# TC_board.net
KiCad netlist of a schematic drawn in EAGLE
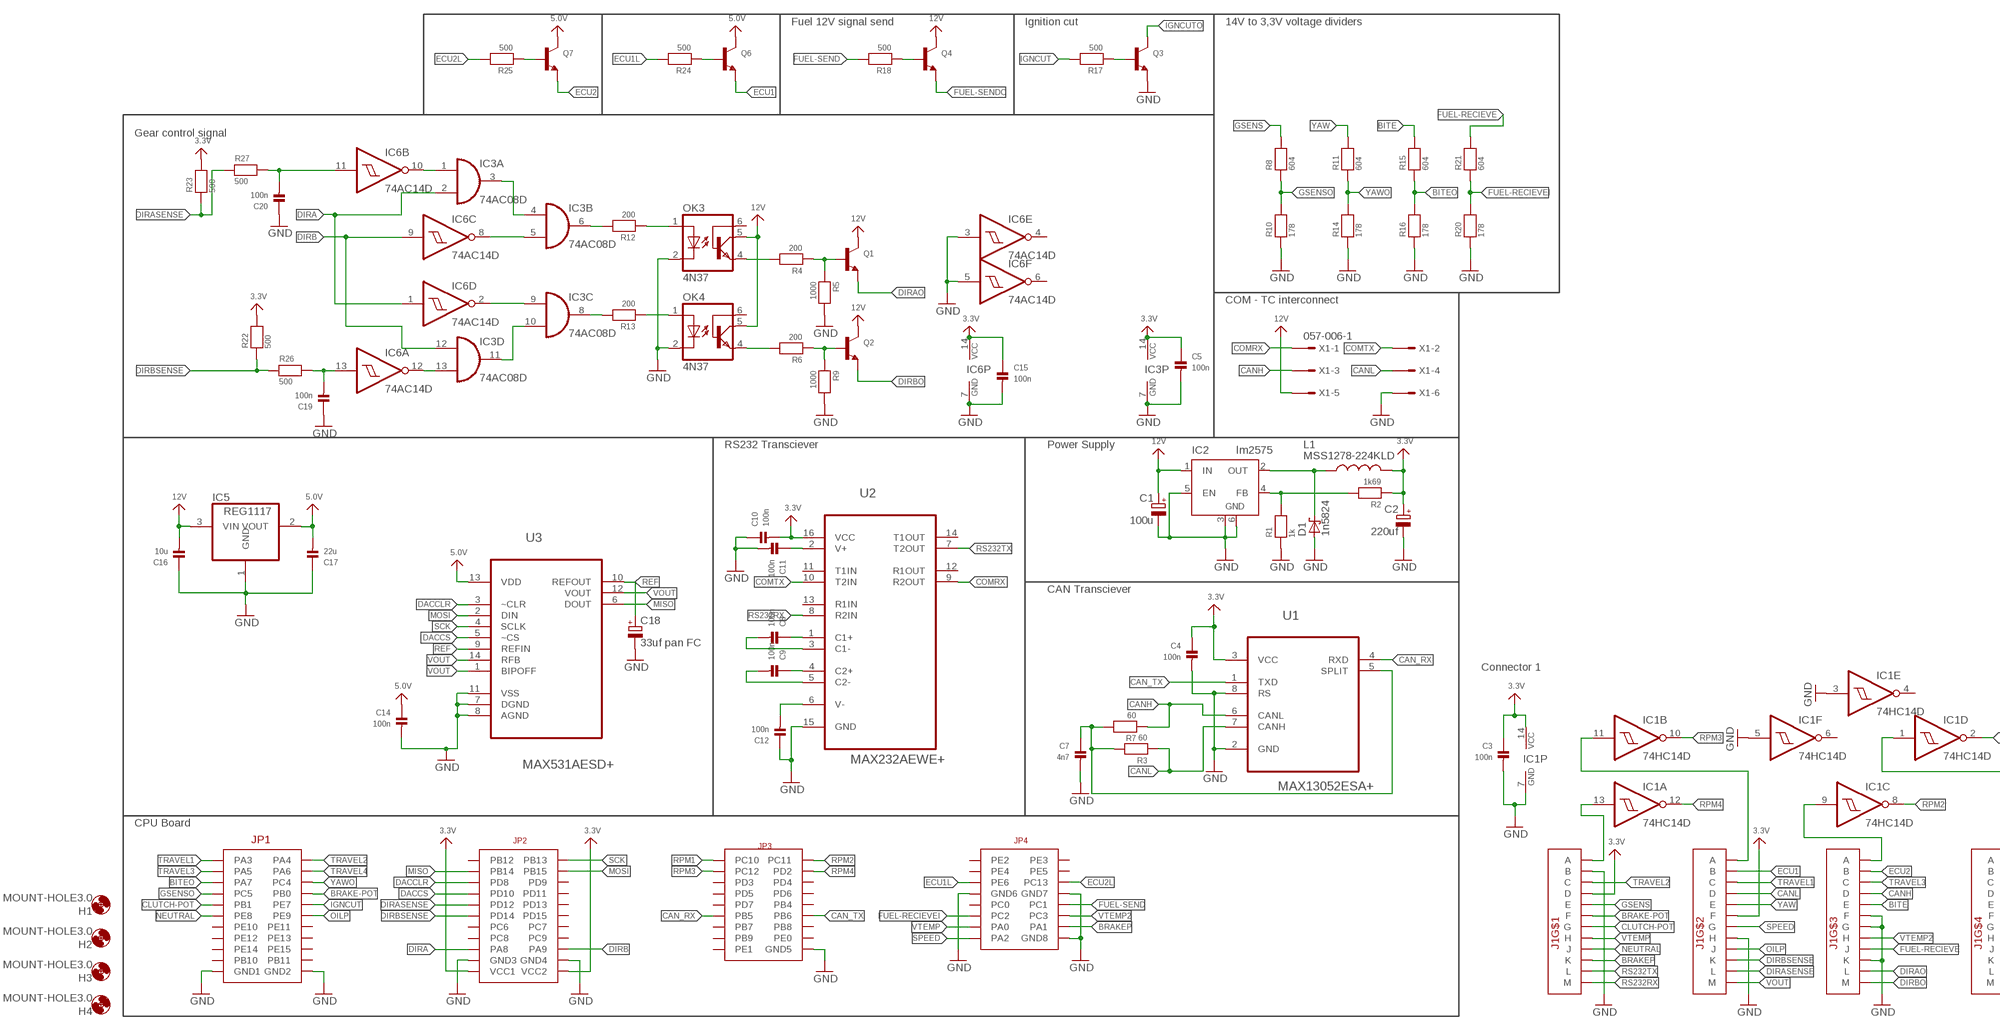
[diagram p0: schematic, sheet 1, part 1 of 2]
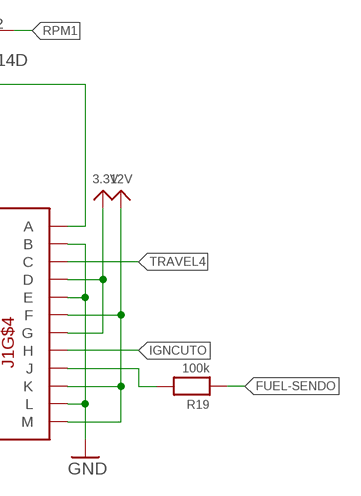
[diagram p1: schematic, sheet 1, part 2 of 2]

(export (version "E")
  (design (tool "Eeschema 10.0.6"))
  (components
    (comp (ref "C1")
      (value "100u")
      (footprint "eagle-import:E2,5-7")
      (libsource (lib "eagle-import") (part "CPOL-EUE2.5-7"))
    )
    (comp (ref "C2")
      (value "220uf")
      (footprint "eagle-import:E3,5-8")
      (libsource (lib "eagle-import") (part "CPOL-EUE3.5-8"))
    )
    (comp (ref "C3")
      (value "100n")
      (footprint "eagle-import:_0603")
      (libsource (lib "eagle-import") (part "CAP_CERAMIC_0603"))
    )
    (comp (ref "C4")
      (value "100n")
      (footprint "eagle-import:_0603")
      (libsource (lib "eagle-import") (part "CAP_CERAMIC_0603"))
    )
    (comp (ref "C5")
      (value "100n")
      (footprint "eagle-import:_0603")
      (libsource (lib "eagle-import") (part "CAP_CERAMIC_0603"))
    )
    (comp (ref "C7")
      (value "4n7")
      (footprint "eagle-import:_0603")
      (libsource (lib "eagle-import") (part "CAP_CERAMIC_0603"))
    )
    (comp (ref "C8")
      (value "100n")
      (footprint "eagle-import:_0603")
      (libsource (lib "eagle-import") (part "CAP_CERAMIC_0603"))
    )
    (comp (ref "C9")
      (value "100n")
      (footprint "eagle-import:_0603")
      (libsource (lib "eagle-import") (part "CAP_CERAMIC_0603"))
    )
    (comp (ref "C10")
      (value "100n")
      (footprint "eagle-import:_0603")
      (libsource (lib "eagle-import") (part "CAP_CERAMIC_0603"))
    )
    (comp (ref "C11")
      (value "100n")
      (footprint "eagle-import:_0603")
      (libsource (lib "eagle-import") (part "CAP_CERAMIC_0603"))
    )
    (comp (ref "C12")
      (value "100n")
      (footprint "eagle-import:_0603")
      (libsource (lib "eagle-import") (part "CAP_CERAMIC_0603"))
    )
    (comp (ref "C14")
      (value "100n")
      (footprint "eagle-import:_0603")
      (libsource (lib "eagle-import") (part "CAP_CERAMIC_0603"))
    )
    (comp (ref "C15")
      (value "100n")
      (footprint "eagle-import:_0603")
      (libsource (lib "eagle-import") (part "CAP_CERAMIC_0603"))
    )
    (comp (ref "C16")
      (value "10u")
      (footprint "eagle-import:_0805")
      (libsource (lib "eagle-import") (part "CAP_CERAMIC_0805"))
    )
    (comp (ref "C17")
      (value "22u")
      (footprint "eagle-import:_0805")
      (libsource (lib "eagle-import") (part "CAP_CERAMIC_0805"))
    )
    (comp (ref "C18")
      (value "33uf pan FC")
      (footprint "eagle-import:UD-5X5,8_NICHICON")
      (libsource (lib "eagle-import") (part "CPOL-EUUD-5X5,8"))
    )
    (comp (ref "C19")
      (value "100n")
      (footprint "eagle-import:_0805")
      (libsource (lib "eagle-import") (part "CAP_CERAMIC_0805"))
    )
    (comp (ref "C20")
      (value "100n")
      (footprint "eagle-import:_0805")
      (libsource (lib "eagle-import") (part "CAP_CERAMIC_0805"))
    )
    (comp (ref "D1")
      (value "1n5824")
      (footprint "eagle-import:F126Z12")
      (libsource (lib "eagle-import") (part "SCHOTTKY-DIODEF126Z12"))
    )
    (comp (ref "H1")
      (value "MOUNT-HOLE3.0")
      (footprint "eagle-import:3,0")
      (libsource (lib "eagle-import") (part "MOUNT-HOLE3.0"))
    )
    (comp (ref "H2")
      (value "MOUNT-HOLE3.0")
      (footprint "eagle-import:3,0")
      (libsource (lib "eagle-import") (part "MOUNT-HOLE3.0"))
    )
    (comp (ref "H3")
      (value "MOUNT-HOLE3.0")
      (footprint "eagle-import:3,0")
      (libsource (lib "eagle-import") (part "MOUNT-HOLE3.0"))
    )
    (comp (ref "H4")
      (value "MOUNT-HOLE3.0")
      (footprint "eagle-import:3,0")
      (libsource (lib "eagle-import") (part "MOUNT-HOLE3.0"))
    )
    (comp (ref "IC1")
      (value "74HC14D")
      (footprint "eagle-import:SO14")
      (libsource (lib "eagle-import") (part "7414DHC"))
    )
    (comp (ref "IC2")
      (value "lm2575")
      (footprint "eagle-import:TO263-5")
      (libsource (lib "eagle-import") (part "LM2596S"))
    )
    (comp (ref "IC3")
      (value "74AC08D")
      (footprint "eagle-import:SO14")
      (libsource (lib "eagle-import") (part "7408DAC"))
    )
    (comp (ref "IC5")
      (value "REG1117")
      (footprint "eagle-import:SOT223")
      (libsource (lib "eagle-import") (part "REG1117"))
    )
    (comp (ref "IC6")
      (value "74AC14D")
      (footprint "eagle-import:SO14")
      (libsource (lib "eagle-import") (part "7414DAC"))
    )
    (comp (ref "J1")
      (value "CON1")
      (footprint "eagle-import:AUTOCONNECTOR")
      (libsource (lib "eagle-import") (part "AUTOCONNECTOR"))
    )
    (comp (ref "L1")
      (value "MSS1278-224KLD")
      (footprint "eagle-import:CDRH125")
      (libsource (lib "eagle-import") (part "INDUCTORPWR"))
    )
    (comp (ref "OK3")
      (value "4N37")
      (footprint "eagle-import:DIL06")
      (fields (field (name "MF") "FAIRCHILD SEMICONDUCTOR"))
      (libsource (lib "eagle-import") (part "4N37"))
    )
    (comp (ref "OK4")
      (value "4N37")
      (footprint "eagle-import:DIL06")
      (fields (field (name "MF") "FAIRCHILD SEMICONDUCTOR"))
      (libsource (lib "eagle-import") (part "4N37"))
    )
    (comp (ref "Q1")
      (value "TRANSISTOR_NPNWIDE")
      (footprint "eagle-import:SOT23-WIDE")
      (libsource (lib "eagle-import") (part "TRANSISTOR_NPNWIDE"))
    )
    (comp (ref "Q2")
      (value "TRANSISTOR_NPNWIDE")
      (footprint "eagle-import:SOT23-WIDE")
      (libsource (lib "eagle-import") (part "TRANSISTOR_NPNWIDE"))
    )
    (comp (ref "Q3")
      (value "TRANSISTOR_NPNWIDE")
      (footprint "eagle-import:SOT23-WIDE")
      (libsource (lib "eagle-import") (part "TRANSISTOR_NPNWIDE"))
    )
    (comp (ref "Q4")
      (value "TRANSISTOR_NPNWIDE")
      (footprint "eagle-import:SOT23-WIDE")
      (libsource (lib "eagle-import") (part "TRANSISTOR_NPNWIDE"))
    )
    (comp (ref "Q6")
      (value "TRANSISTOR_NPNWIDE")
      (footprint "eagle-import:SOT23-WIDE")
      (libsource (lib "eagle-import") (part "TRANSISTOR_NPNWIDE"))
    )
    (comp (ref "Q7")
      (value "TRANSISTOR_NPNWIDE")
      (footprint "eagle-import:SOT23-WIDE")
      (libsource (lib "eagle-import") (part "TRANSISTOR_NPNWIDE"))
    )
    (comp (ref "R1")
      (value "1k")
      (footprint "eagle-import:_0603")
      (libsource (lib "eagle-import") (part "RESISTOR_0603"))
    )
    (comp (ref "R2")
      (value "1k69")
      (footprint "eagle-import:_0603")
      (libsource (lib "eagle-import") (part "RESISTOR_0603"))
    )
    (comp (ref "R3")
      (value "60")
      (footprint "eagle-import:_0603")
      (libsource (lib "eagle-import") (part "RESISTOR_0603"))
    )
    (comp (ref "R4")
      (value "200")
      (footprint "eagle-import:_0603")
      (libsource (lib "eagle-import") (part "RESISTOR_0603"))
    )
    (comp (ref "R5")
      (value "1000")
      (footprint "eagle-import:_0603")
      (libsource (lib "eagle-import") (part "RESISTOR_0603"))
    )
    (comp (ref "R6")
      (value "200")
      (footprint "eagle-import:_0603")
      (libsource (lib "eagle-import") (part "RESISTOR_0603"))
    )
    (comp (ref "R7")
      (value "60")
      (footprint "eagle-import:_0603")
      (libsource (lib "eagle-import") (part "RESISTOR_0603"))
    )
    (comp (ref "R8")
      (value "604")
      (footprint "eagle-import:_0603")
      (libsource (lib "eagle-import") (part "RESISTOR_0603"))
    )
    (comp (ref "R9")
      (value "1000")
      (footprint "eagle-import:_0603")
      (libsource (lib "eagle-import") (part "RESISTOR_0603"))
    )
    (comp (ref "R10")
      (value "178")
      (footprint "eagle-import:_0603")
      (libsource (lib "eagle-import") (part "RESISTOR_0603"))
    )
    (comp (ref "R11")
      (value "604")
      (footprint "eagle-import:_0603")
      (libsource (lib "eagle-import") (part "RESISTOR_0603"))
    )
    (comp (ref "R12")
      (value "200")
      (footprint "eagle-import:_0603")
      (libsource (lib "eagle-import") (part "RESISTOR_0603"))
    )
    (comp (ref "R13")
      (value "200")
      (footprint "eagle-import:_0603")
      (libsource (lib "eagle-import") (part "RESISTOR_0603"))
    )
    (comp (ref "R14")
      (value "178")
      (footprint "eagle-import:_0603")
      (libsource (lib "eagle-import") (part "RESISTOR_0603"))
    )
    (comp (ref "R15")
      (value "604")
      (footprint "eagle-import:_0603")
      (libsource (lib "eagle-import") (part "RESISTOR_0603"))
    )
    (comp (ref "R16")
      (value "178")
      (footprint "eagle-import:_0603")
      (libsource (lib "eagle-import") (part "RESISTOR_0603"))
    )
    (comp (ref "R17")
      (value "500")
      (footprint "eagle-import:_0603")
      (libsource (lib "eagle-import") (part "RESISTOR_0603"))
    )
    (comp (ref "R18")
      (value "500")
      (footprint "eagle-import:_0603")
      (libsource (lib "eagle-import") (part "RESISTOR_0603"))
    )
    (comp (ref "R19")
      (value "100k")
      (footprint "eagle-import:_0603")
      (libsource (lib "eagle-import") (part "RESISTOR_0603"))
    )
    (comp (ref "R20")
      (value "178")
      (footprint "eagle-import:_0603")
      (libsource (lib "eagle-import") (part "RESISTOR_0603"))
    )
    (comp (ref "R21")
      (value "604")
      (footprint "eagle-import:_0603")
      (libsource (lib "eagle-import") (part "RESISTOR_0603"))
    )
    (comp (ref "R22")
      (value "500")
      (footprint "eagle-import:_0603")
      (libsource (lib "eagle-import") (part "RESISTOR_0603"))
    )
    (comp (ref "R23")
      (value "500")
      (footprint "eagle-import:_0603")
      (libsource (lib "eagle-import") (part "RESISTOR_0603"))
    )
    (comp (ref "R24")
      (value "500")
      (footprint "eagle-import:_0603")
      (libsource (lib "eagle-import") (part "RESISTOR_0603"))
    )
    (comp (ref "R25")
      (value "500")
      (footprint "eagle-import:_0603")
      (libsource (lib "eagle-import") (part "RESISTOR_0603"))
    )
    (comp (ref "R26")
      (value "500")
      (footprint "eagle-import:_0603")
      (libsource (lib "eagle-import") (part "RESISTOR_0603"))
    )
    (comp (ref "R27")
      (value "500")
      (footprint "eagle-import:_0603")
      (libsource (lib "eagle-import") (part "RESISTOR_0603"))
    )
    (comp (ref "U$1")
      (value "CPU-BOARD")
      (footprint "eagle-import:CPU-BOARD-JP1")
      (libsource (lib "eagle-import") (part "CPU-BOARD"))
    )
    (comp (ref "U1")
      (value "MAX13052ESA+")
      (footprint "eagle-import:SOIC127P600X175-8N")
      (libsource (lib "eagle-import") (part "MAX13052ESA+"))
    )
    (comp (ref "U2")
      (value "MAX232AEWE+")
      (footprint "eagle-import:SOIC127P1032X265-16N")
      (libsource (lib "eagle-import") (part "MAX232AEWE+"))
    )
    (comp (ref "U3")
      (value "MAX531AESD+")
      (footprint "eagle-import:SOIC127P600X175-14N")
      (libsource (lib "eagle-import") (part "MAX531AESD+"))
    )
    (comp (ref "X1")
      (value "057-006-1")
      (footprint "eagle-import:057-006-1")
      (libsource (lib "eagle-import") (part "057-006-1"))
    )
  )
  (nets
    (net (code "1") (name "3.3V") (class "Default")
      (node (ref "C10") (pin "2") (pinfunction "P$2_2") (pintype "passive"))
      (node (ref "C15") (pin "1") (pinfunction "P$1_1") (pintype "passive"))
      (node (ref "C2") (pin "+") (pinfunction "+_+") (pintype "passive"))
      (node (ref "C3") (pin "1") (pinfunction "P$1_1") (pintype "passive"))
      (node (ref "C4") (pin "1") (pinfunction "P$1_1") (pintype "passive"))
      (node (ref "C5") (pin "1") (pinfunction "P$1_1") (pintype "passive"))
      (node (ref "IC1") (pin "14") (pinfunction "VCC_14") (pintype "power_in"))
      (node (ref "IC3") (pin "14") (pinfunction "VCC_14") (pintype "power_in"))
      (node (ref "IC6") (pin "14") (pinfunction "VCC_14") (pintype "power_in"))
      (node (ref "J1") (pin "D1") (pinfunction "D_D1") (pintype "bidirectional"))
      (node (ref "J1") (pin "D4") (pinfunction "D_D4") (pintype "bidirectional"))
      (node (ref "J1") (pin "F2") (pinfunction "F_F2") (pintype "bidirectional"))
      (node (ref "J1") (pin "G4") (pinfunction "G_G4") (pintype "bidirectional"))
      (node (ref "L1") (pin "2") (pinfunction "2_2") (pintype "passive"))
      (node (ref "R2") (pin "1") (pinfunction "1_1") (pintype "passive"))
      (node (ref "R22") (pin "2") (pinfunction "2_2") (pintype "passive"))
      (node (ref "R23") (pin "2") (pinfunction "2_2") (pintype "passive"))
      (node (ref "U$1") (pin "P$43") (pinfunction "VCC1_P$43") (pintype "bidirectional"))
      (node (ref "U$1") (pin "P$44") (pinfunction "VCC2_P$44") (pintype "bidirectional"))
      (node (ref "U1") (pin "3") (pinfunction "VCC_3") (pintype "power_in"))
      (node (ref "U2") (pin "16") (pinfunction "VCC_16") (pintype "power_in"))
    )
    (net (code "2") (name "5.0V") (class "Default")
      (node (ref "C14") (pin "1") (pinfunction "P$1_1") (pintype "passive"))
      (node (ref "C17") (pin "2") (pinfunction "P$2_2") (pintype "passive"))
      (node (ref "IC5") (pin "2") (pinfunction "VOUT_2") (pintype "output"))
      (node (ref "Q6") (pin "3") (pinfunction "C_3") (pintype "passive"))
      (node (ref "Q7") (pin "3") (pinfunction "C_3") (pintype "passive"))
      (node (ref "U3") (pin "13") (pinfunction "VDD_13") (pintype "power_in"))
    )
    (net (code "3") (name "12V") (class "Default")
      (node (ref "C1") (pin "+") (pinfunction "+_+") (pintype "passive"))
      (node (ref "C16") (pin "2") (pinfunction "P$2_2") (pintype "passive"))
      (node (ref "IC2") (pin "1") (pinfunction "IN_1") (pintype "input"))
      (node (ref "IC5") (pin "3") (pinfunction "VIN_3") (pintype "input"))
      (node (ref "J1") (pin "F4") (pinfunction "F_F4") (pintype "bidirectional"))
      (node (ref "J1") (pin "K4") (pinfunction "K_K4") (pintype "bidirectional"))
      (node (ref "J1") (pin "M4") (pinfunction "M_M4") (pintype "bidirectional"))
      (node (ref "OK3") (pin "5") (pinfunction "COL_5") (pintype "passive"))
      (node (ref "OK4") (pin "5") (pinfunction "COL_5") (pintype "passive"))
      (node (ref "Q1") (pin "3") (pinfunction "C_3") (pintype "passive"))
      (node (ref "Q2") (pin "3") (pinfunction "C_3") (pintype "passive"))
      (node (ref "Q4") (pin "3") (pinfunction "C_3") (pintype "passive"))
      (node (ref "X1") (pin "5") (pinfunction "S_5") (pintype "passive"))
    )
    (net (code "4") (name "BITE") (class "Default")
      (node (ref "J1") (pin "E3") (pinfunction "E_E3") (pintype "bidirectional"))
      (node (ref "R15") (pin "2") (pinfunction "2_2") (pintype "passive"))
    )
    (net (code "5") (name "BITEO") (class "Default")
      (node (ref "R15") (pin "1") (pinfunction "1_1") (pintype "passive"))
      (node (ref "R16") (pin "2") (pinfunction "2_2") (pintype "passive"))
      (node (ref "U$1") (pin "P$5") (pinfunction "PA7_P$5") (pintype "bidirectional"))
    )
    (net (code "6") (name "BRAKE-POT") (class "Default")
      (node (ref "J1") (pin "F1") (pinfunction "F_F1") (pintype "bidirectional"))
      (node (ref "U$1") (pin "P$8") (pinfunction "PB0_P$8") (pintype "bidirectional"))
    )
    (net (code "7") (name "BRAKEP") (class "Default")
      (node (ref "J1") (pin "K1") (pinfunction "K_K1") (pintype "bidirectional"))
      (node (ref "U$1") (pin "P$76") (pinfunction "PA1_P$76") (pintype "bidirectional"))
    )
    (net (code "8") (name "CANH") (class "Default")
      (node (ref "J1") (pin "D3") (pinfunction "D_D3") (pintype "bidirectional"))
      (node (ref "R7") (pin "1") (pinfunction "1_1") (pintype "passive"))
      (node (ref "U1") (pin "6") (pinfunction "CANL_6") (pintype "input"))
      (node (ref "X1") (pin "3") (pinfunction "S_3") (pintype "passive"))
    )
    (net (code "9") (name "CANL") (class "Default")
      (node (ref "J1") (pin "D2") (pinfunction "D_D2") (pintype "bidirectional"))
      (node (ref "R3") (pin "1") (pinfunction "1_1") (pintype "passive"))
      (node (ref "U1") (pin "7") (pinfunction "CANH_7") (pintype "input"))
      (node (ref "X1") (pin "4") (pinfunction "S_4") (pintype "passive"))
    )
    (net (code "10") (name "CAN_RX") (class "Default")
      (node (ref "U$1") (pin "P$55") (pinfunction "PB5_P$55") (pintype "bidirectional"))
      (node (ref "U1") (pin "4") (pinfunction "RXD_4") (pintype "output"))
    )
    (net (code "11") (name "CAN_TX") (class "Default")
      (node (ref "U$1") (pin "P$56") (pinfunction "PB6_P$56") (pintype "bidirectional"))
      (node (ref "U1") (pin "1") (pinfunction "TXD_1") (pintype "input"))
    )
    (net (code "12") (name "CLUTCH-POT") (class "Default")
      (node (ref "J1") (pin "G1") (pinfunction "G_G1") (pintype "bidirectional"))
      (node (ref "U$1") (pin "P$9") (pinfunction "PB1_P$9") (pintype "bidirectional"))
    )
    (net (code "13") (name "COMRX") (class "Default")
      (node (ref "U2") (pin "9") (pinfunction "R2OUT_9") (pintype "output"))
      (node (ref "X1") (pin "1") (pinfunction "S_1") (pintype "passive"))
    )
    (net (code "14") (name "COMTX") (class "Default")
      (node (ref "U2") (pin "10") (pinfunction "T2IN_10") (pintype "input"))
      (node (ref "X1") (pin "2") (pinfunction "S_2") (pintype "passive"))
    )
    (net (code "15") (name "DACCLR") (class "Default")
      (node (ref "U$1") (pin "P$27") (pinfunction "PD8_P$27") (pintype "bidirectional"))
      (node (ref "U3") (pin "3") (pinfunction "~{CLR}_3") (pintype "input"))
    )
    (net (code "16") (name "DACCS") (class "Default")
      (node (ref "U$1") (pin "P$29") (pinfunction "PD10_P$29") (pintype "bidirectional"))
      (node (ref "U3") (pin "5") (pinfunction "~{CS}_5") (pintype "input"))
    )
    (net (code "17") (name "DIRA") (class "Default")
      (node (ref "IC3") (pin "2") (pinfunction "I1_2") (pintype "input"))
      (node (ref "IC6") (pin "1") (pinfunction "I_1") (pintype "input"))
      (node (ref "U$1") (pin "P$39") (pinfunction "PA8_P$39") (pintype "bidirectional"))
    )
    (net (code "18") (name "DIRAO") (class "Default")
      (node (ref "J1") (pin "L3") (pinfunction "L_L3") (pintype "bidirectional"))
      (node (ref "Q1") (pin "2") (pinfunction "E_2") (pintype "passive"))
    )
    (net (code "19") (name "DIRASENSE") (class "Default")
      (node (ref "J1") (pin "L2") (pinfunction "L_L2") (pintype "bidirectional"))
      (node (ref "R23") (pin "1") (pinfunction "1_1") (pintype "passive"))
      (node (ref "R27") (pin "1") (pinfunction "1_1") (pintype "passive"))
      (node (ref "U$1") (pin "P$31") (pinfunction "PD12_P$31") (pintype "bidirectional"))
    )
    (net (code "20") (name "DIRB") (class "Default")
      (node (ref "IC3") (pin "12") (pinfunction "I0_12") (pintype "input"))
      (node (ref "IC6") (pin "9") (pinfunction "I_9") (pintype "input"))
      (node (ref "U$1") (pin "P$40") (pinfunction "PA9_P$40") (pintype "bidirectional"))
    )
    (net (code "21") (name "DIRBO") (class "Default")
      (node (ref "J1") (pin "M3") (pinfunction "M_M3") (pintype "bidirectional"))
      (node (ref "Q2") (pin "2") (pinfunction "E_2") (pintype "passive"))
    )
    (net (code "22") (name "DIRBSENSE") (class "Default")
      (node (ref "J1") (pin "K2") (pinfunction "K_K2") (pintype "bidirectional"))
      (node (ref "R22") (pin "1") (pinfunction "1_1") (pintype "passive"))
      (node (ref "R26") (pin "1") (pinfunction "1_1") (pintype "passive"))
      (node (ref "U$1") (pin "P$33") (pinfunction "PD14_P$33") (pintype "bidirectional"))
    )
    (net (code "23") (name "ECU1") (class "Default")
      (node (ref "J1") (pin "B2") (pinfunction "B_B2") (pintype "bidirectional"))
      (node (ref "Q6") (pin "2") (pinfunction "E_2") (pintype "passive"))
    )
    (net (code "24") (name "ECU1L") (class "Default")
      (node (ref "R24") (pin "2") (pinfunction "2_2") (pintype "passive"))
      (node (ref "U$1") (pin "P$67") (pinfunction "PE6_P$67") (pintype "bidirectional"))
    )
    (net (code "25") (name "ECU2") (class "Default")
      (node (ref "J1") (pin "B3") (pinfunction "B_B3") (pintype "bidirectional"))
      (node (ref "Q7") (pin "2") (pinfunction "E_2") (pintype "passive"))
    )
    (net (code "26") (name "ECU2L") (class "Default")
      (node (ref "R25") (pin "2") (pinfunction "2_2") (pintype "passive"))
      (node (ref "U$1") (pin "P$68") (pinfunction "PC13_P$68") (pintype "bidirectional"))
    )
    (net (code "27") (name "FUEL-RECIEVE") (class "Default")
      (node (ref "J1") (pin "J3") (pinfunction "J_J3") (pintype "bidirectional"))
      (node (ref "R21") (pin "2") (pinfunction "2_2") (pintype "passive"))
    )
    (net (code "28") (name "FUEL-RECIEVEI") (class "Default")
      (node (ref "R20") (pin "2") (pinfunction "2_2") (pintype "passive"))
      (node (ref "R21") (pin "1") (pinfunction "1_1") (pintype "passive"))
      (node (ref "U$1") (pin "P$73") (pinfunction "PC2_P$73") (pintype "bidirectional"))
    )
    (net (code "29") (name "FUEL-SEND") (class "Default")
      (node (ref "R18") (pin "2") (pinfunction "2_2") (pintype "passive"))
      (node (ref "U$1") (pin "P$72") (pinfunction "PC1_P$72") (pintype "bidirectional"))
    )
    (net (code "30") (name "FUEL-SENDO") (class "Default")
      (node (ref "Q4") (pin "2") (pinfunction "E_2") (pintype "passive"))
      (node (ref "R19") (pin "1") (pinfunction "1_1") (pintype "passive"))
    )
    (net (code "31") (name "GND") (class "Default")
      (node (ref "C1") (pin "-") (pinfunction "-_-") (pintype "passive"))
      (node (ref "C10") (pin "1") (pinfunction "P$1_1") (pintype "passive"))
      (node (ref "C11") (pin "2") (pinfunction "P$2_2") (pintype "passive"))
      (node (ref "C12") (pin "1") (pinfunction "P$1_1") (pintype "passive"))
      (node (ref "C14") (pin "2") (pinfunction "P$2_2") (pintype "passive"))
      (node (ref "C15") (pin "2") (pinfunction "P$2_2") (pintype "passive"))
      (node (ref "C16") (pin "1") (pinfunction "P$1_1") (pintype "passive"))
      (node (ref "C17") (pin "1") (pinfunction "P$1_1") (pintype "passive"))
      (node (ref "C18") (pin "-") (pinfunction "-_-") (pintype "passive"))
      (node (ref "C19") (pin "1") (pinfunction "P$1_1") (pintype "passive"))
      (node (ref "C2") (pin "-") (pinfunction "-_-") (pintype "passive"))
      (node (ref "C20") (pin "1") (pinfunction "P$1_1") (pintype "passive"))
      (node (ref "C3") (pin "2") (pinfunction "P$2_2") (pintype "passive"))
      (node (ref "C4") (pin "2") (pinfunction "P$2_2") (pintype "passive"))
      (node (ref "C5") (pin "2") (pinfunction "P$2_2") (pintype "passive"))
      (node (ref "C7") (pin "2") (pinfunction "P$2_2") (pintype "passive"))
      (node (ref "D1") (pin "A") (pinfunction "A_A") (pintype "passive"))
      (node (ref "IC1") (pin "3") (pinfunction "I_3") (pintype "input"))
      (node (ref "IC1") (pin "5") (pinfunction "I_5") (pintype "input"))
      (node (ref "IC1") (pin "7") (pinfunction "GND_7") (pintype "power_in"))
      (node (ref "IC2") (pin "3") (pinfunction "GND_3") (pintype "power_in"))
      (node (ref "IC2") (pin "5") (pinfunction "EN_5") (pintype "input"))
      (node (ref "IC2") (pin "6") (pinfunction "GND_6") (pintype "power_in"))
      (node (ref "IC3") (pin "7") (pinfunction "GND_7") (pintype "power_in"))
      (node (ref "IC5") (pin "1") (pinfunction "GND_1") (pintype "power_in"))
      (node (ref "IC6") (pin "3") (pinfunction "I_3") (pintype "input"))
      (node (ref "IC6") (pin "5") (pinfunction "I_5") (pintype "input"))
      (node (ref "IC6") (pin "7") (pinfunction "GND_7") (pintype "power_in"))
      (node (ref "J1") (pin "B1") (pinfunction "B_B1") (pintype "bidirectional"))
      (node (ref "J1") (pin "B4") (pinfunction "B_B4") (pintype "bidirectional"))
      (node (ref "J1") (pin "E4") (pinfunction "E_E4") (pintype "bidirectional"))
      (node (ref "J1") (pin "F3") (pinfunction "F_F3") (pintype "bidirectional"))
      (node (ref "J1") (pin "G3") (pinfunction "G_G3") (pintype "bidirectional"))
      (node (ref "J1") (pin "H2") (pinfunction "H_H2") (pintype "bidirectional"))
      (node (ref "J1") (pin "K3") (pinfunction "K_K3") (pintype "bidirectional"))
      (node (ref "J1") (pin "L4") (pinfunction "L_L4") (pintype "bidirectional"))
      (node (ref "OK3") (pin "2") (pinfunction "C_2") (pintype "passive"))
      (node (ref "OK4") (pin "2") (pinfunction "C_2") (pintype "passive"))
      (node (ref "Q3") (pin "2") (pinfunction "E_2") (pintype "passive"))
      (node (ref "R1") (pin "1") (pinfunction "1_1") (pintype "passive"))
      (node (ref "R10") (pin "1") (pinfunction "1_1") (pintype "passive"))
      (node (ref "R14") (pin "1") (pinfunction "1_1") (pintype "passive"))
      (node (ref "R16") (pin "1") (pinfunction "1_1") (pintype "passive"))
      (node (ref "R20") (pin "1") (pinfunction "1_1") (pintype "passive"))
      (node (ref "R5") (pin "2") (pinfunction "2_2") (pintype "passive"))
      (node (ref "R9") (pin "2") (pinfunction "2_2") (pintype "passive"))
      (node (ref "U$1") (pin "P$19") (pinfunction "GND1_P$19") (pintype "bidirectional"))
      (node (ref "U$1") (pin "P$20") (pinfunction "GND2_P$20") (pintype "bidirectional"))
      (node (ref "U$1") (pin "P$41") (pinfunction "GND3_P$41") (pintype "bidirectional"))
      (node (ref "U$1") (pin "P$42") (pinfunction "GND4_P$42") (pintype "bidirectional"))
      (node (ref "U$1") (pin "P$62") (pinfunction "GND5_P$62") (pintype "bidirectional"))
      (node (ref "U$1") (pin "P$69") (pinfunction "GND6_P$69") (pintype "bidirectional"))
      (node (ref "U$1") (pin "P$70") (pinfunction "GND7_P$70") (pintype "bidirectional"))
      (node (ref "U$1") (pin "P$78") (pinfunction "GND8_P$78") (pintype "bidirectional"))
      (node (ref "U1") (pin "2") (pinfunction "GND_2") (pintype "passive"))
      (node (ref "U1") (pin "8") (pinfunction "RS_8") (pintype "input"))
      (node (ref "U2") (pin "15") (pinfunction "GND_15") (pintype "passive"))
      (node (ref "U3") (pin "11") (pinfunction "VSS_11") (pintype "power_in"))
      (node (ref "U3") (pin "7") (pinfunction "DGND_7") (pintype "passive"))
      (node (ref "U3") (pin "8") (pinfunction "AGND_8") (pintype "passive"))
      (node (ref "X1") (pin "6") (pinfunction "S_6") (pintype "passive"))
    )
    (net (code "32") (name "GSENS") (class "Default")
      (node (ref "J1") (pin "E1") (pinfunction "E_E1") (pintype "bidirectional"))
      (node (ref "R8") (pin "2") (pinfunction "2_2") (pintype "passive"))
    )
    (net (code "33") (name "GSENSO") (class "Default")
      (node (ref "R10") (pin "2") (pinfunction "2_2") (pintype "passive"))
      (node (ref "R8") (pin "1") (pinfunction "1_1") (pintype "passive"))
      (node (ref "U$1") (pin "P$7") (pinfunction "PC5_P$7") (pintype "bidirectional"))
    )
    (net (code "34") (name "IGNCUT") (class "Default")
      (node (ref "R17") (pin "2") (pinfunction "2_2") (pintype "passive"))
      (node (ref "U$1") (pin "P$10") (pinfunction "PE7_P$10") (pintype "bidirectional"))
    )
    (net (code "35") (name "IGNCUTO") (class "Default")
      (node (ref "J1") (pin "H4") (pinfunction "H_H4") (pintype "bidirectional"))
      (node (ref "Q3") (pin "3") (pinfunction "C_3") (pintype "passive"))
    )
    (net (code "36") (name "MISO") (class "Default")
      (node (ref "U$1") (pin "P$25") (pinfunction "PB14_P$25") (pintype "bidirectional"))
      (node (ref "U3") (pin "6") (pinfunction "DOUT_6") (pintype "output"))
    )
    (net (code "37") (name "MOSI") (class "Default")
      (node (ref "U$1") (pin "P$26") (pinfunction "PB15_P$26") (pintype "bidirectional"))
      (node (ref "U3") (pin "2") (pinfunction "DIN_2") (pintype "input"))
    )
    (net (code "38") (name "NEUTRAL") (class "Default")
      (node (ref "J1") (pin "J1") (pinfunction "J_J1") (pintype "bidirectional"))
      (node (ref "U$1") (pin "P$11") (pinfunction "PE8_P$11") (pintype "bidirectional"))
    )
    (net (code "39") (name "Net-(C7-P$1)") (class "Default")
      (node (ref "C7") (pin "1") (pinfunction "P$1_1") (pintype "passive"))
      (node (ref "R3") (pin "2") (pinfunction "2_2") (pintype "passive"))
      (node (ref "R7") (pin "2") (pinfunction "2_2") (pintype "passive"))
      (node (ref "U1") (pin "5") (pinfunction "SPLIT_5") (pintype "output"))
    )
    (net (code "40") (name "Net-(C8-P$1)") (class "Default")
      (node (ref "C8") (pin "1") (pinfunction "P$1_1") (pintype "passive"))
      (node (ref "U2") (pin "1") (pinfunction "C1+_1") (pintype "input"))
    )
    (net (code "41") (name "Net-(C8-P$2)") (class "Default")
      (node (ref "C8") (pin "2") (pinfunction "P$2_2") (pintype "passive"))
      (node (ref "U2") (pin "3") (pinfunction "C1-_3") (pintype "input"))
    )
    (net (code "42") (name "Net-(C9-P$1)") (class "Default")
      (node (ref "C9") (pin "1") (pinfunction "P$1_1") (pintype "passive"))
      (node (ref "U2") (pin "4") (pinfunction "C2+_4") (pintype "input"))
    )
    (net (code "43") (name "Net-(C9-P$2)") (class "Default")
      (node (ref "C9") (pin "2") (pinfunction "P$2_2") (pintype "passive"))
      (node (ref "U2") (pin "5") (pinfunction "C2-_5") (pintype "input"))
    )
    (net (code "44") (name "Net-(C11-P$1)") (class "Default")
      (node (ref "C11") (pin "1") (pinfunction "P$1_1") (pintype "passive"))
      (node (ref "U2") (pin "2") (pinfunction "V+_2") (pintype "power_in"))
    )
    (net (code "45") (name "Net-(C12-P$2)") (class "Default")
      (node (ref "C12") (pin "2") (pinfunction "P$2_2") (pintype "passive"))
      (node (ref "U2") (pin "6") (pinfunction "V-_6") (pintype "power_in"))
    )
    (net (code "46") (name "Net-(C19-P$2)") (class "Default")
      (node (ref "C19") (pin "2") (pinfunction "P$2_2") (pintype "passive"))
      (node (ref "IC6") (pin "13") (pinfunction "I_13") (pintype "input"))
      (node (ref "R26") (pin "2") (pinfunction "2_2") (pintype "passive"))
    )
    (net (code "47") (name "Net-(C20-P$2)") (class "Default")
      (node (ref "C20") (pin "2") (pinfunction "P$2_2") (pintype "passive"))
      (node (ref "IC6") (pin "11") (pinfunction "I_11") (pintype "input"))
      (node (ref "R27") (pin "2") (pinfunction "2_2") (pintype "passive"))
    )
    (net (code "48") (name "Net-(IC1A-I)") (class "Default")
      (node (ref "IC1") (pin "13") (pinfunction "I_13") (pintype "input"))
      (node (ref "J1") (pin "A1") (pinfunction "A_A1") (pintype "bidirectional"))
    )
    (net (code "49") (name "Net-(IC1B-I)") (class "Default")
      (node (ref "IC1") (pin "11") (pinfunction "I_11") (pintype "input"))
      (node (ref "J1") (pin "A2") (pinfunction "A_A2") (pintype "bidirectional"))
    )
    (net (code "50") (name "Net-(IC1C-I)") (class "Default")
      (node (ref "IC1") (pin "9") (pinfunction "I_9") (pintype "input"))
      (node (ref "J1") (pin "A3") (pinfunction "A_A3") (pintype "bidirectional"))
    )
    (net (code "51") (name "Net-(IC1D-I)") (class "Default")
      (node (ref "IC1") (pin "1") (pinfunction "I_1") (pintype "input"))
      (node (ref "J1") (pin "A4") (pinfunction "A_A4") (pintype "bidirectional"))
    )
    (net (code "52") (name "Net-(IC2-FB)") (class "Default")
      (node (ref "IC2") (pin "4") (pinfunction "FB_4") (pintype "input"))
      (node (ref "R1") (pin "2") (pinfunction "2_2") (pintype "passive"))
      (node (ref "R2") (pin "2") (pinfunction "2_2") (pintype "passive"))
    )
    (net (code "53") (name "Net-(IC2-OUT)") (class "Default")
      (node (ref "D1") (pin "C") (pinfunction "C_C") (pintype "passive"))
      (node (ref "IC2") (pin "2") (pinfunction "OUT_2") (pintype "output"))
      (node (ref "L1") (pin "1") (pinfunction "1_1") (pintype "passive"))
    )
    (net (code "54") (name "Net-(IC3A-I0)") (class "Default")
      (node (ref "IC3") (pin "1") (pinfunction "I0_1") (pintype "input"))
      (node (ref "IC6") (pin "10") (pinfunction "O_10") (pintype "output"))
    )
    (net (code "55") (name "Net-(IC3A-O)") (class "Default")
      (node (ref "IC3") (pin "3") (pinfunction "O_3") (pintype "output"))
      (node (ref "IC3") (pin "4") (pinfunction "I0_4") (pintype "input"))
    )
    (net (code "56") (name "Net-(IC3B-I1)") (class "Default")
      (node (ref "IC3") (pin "5") (pinfunction "I1_5") (pintype "input"))
      (node (ref "IC6") (pin "8") (pinfunction "O_8") (pintype "output"))
    )
    (net (code "57") (name "Net-(IC3B-O)") (class "Default")
      (node (ref "IC3") (pin "6") (pinfunction "O_6") (pintype "output"))
      (node (ref "R12") (pin "2") (pinfunction "2_2") (pintype "passive"))
    )
    (net (code "58") (name "Net-(IC3C-I0)") (class "Default")
      (node (ref "IC3") (pin "9") (pinfunction "I0_9") (pintype "input"))
      (node (ref "IC6") (pin "2") (pinfunction "O_2") (pintype "output"))
    )
    (net (code "59") (name "Net-(IC3C-I1)") (class "Default")
      (node (ref "IC3") (pin "10") (pinfunction "I1_10") (pintype "input"))
      (node (ref "IC3") (pin "11") (pinfunction "O_11") (pintype "output"))
    )
    (net (code "60") (name "Net-(IC3C-O)") (class "Default")
      (node (ref "IC3") (pin "8") (pinfunction "O_8") (pintype "output"))
      (node (ref "R13") (pin "2") (pinfunction "2_2") (pintype "passive"))
    )
    (net (code "61") (name "Net-(IC3D-I1)") (class "Default")
      (node (ref "IC3") (pin "13") (pinfunction "I1_13") (pintype "input"))
      (node (ref "IC6") (pin "12") (pinfunction "O_12") (pintype "output"))
    )
    (net (code "62") (name "Net-(J1D-J)") (class "Default")
      (node (ref "J1") (pin "J4") (pinfunction "J_J4") (pintype "bidirectional"))
      (node (ref "R19") (pin "2") (pinfunction "2_2") (pintype "passive"))
    )
    (net (code "63") (name "Net-(OK3-A)") (class "Default")
      (node (ref "OK3") (pin "1") (pinfunction "A_1") (pintype "passive"))
      (node (ref "R12") (pin "1") (pinfunction "1_1") (pintype "passive"))
    )
    (net (code "64") (name "Net-(OK3-EMI)") (class "Default")
      (node (ref "OK3") (pin "4") (pinfunction "EMI_4") (pintype "passive"))
      (node (ref "R4") (pin "2") (pinfunction "2_2") (pintype "passive"))
    )
    (net (code "65") (name "Net-(OK4-A)") (class "Default")
      (node (ref "OK4") (pin "1") (pinfunction "A_1") (pintype "passive"))
      (node (ref "R13") (pin "1") (pinfunction "1_1") (pintype "passive"))
    )
    (net (code "66") (name "Net-(OK4-EMI)") (class "Default")
      (node (ref "OK4") (pin "4") (pinfunction "EMI_4") (pintype "passive"))
      (node (ref "R6") (pin "2") (pinfunction "2_2") (pintype "passive"))
    )
    (net (code "67") (name "Net-(Q1-B)") (class "Default")
      (node (ref "Q1") (pin "1") (pinfunction "B_1") (pintype "passive"))
      (node (ref "R4") (pin "1") (pinfunction "1_1") (pintype "passive"))
      (node (ref "R5") (pin "1") (pinfunction "1_1") (pintype "passive"))
    )
    (net (code "68") (name "Net-(Q2-B)") (class "Default")
      (node (ref "Q2") (pin "1") (pinfunction "B_1") (pintype "passive"))
      (node (ref "R6") (pin "1") (pinfunction "1_1") (pintype "passive"))
      (node (ref "R9") (pin "1") (pinfunction "1_1") (pintype "passive"))
    )
    (net (code "69") (name "Net-(Q3-B)") (class "Default")
      (node (ref "Q3") (pin "1") (pinfunction "B_1") (pintype "passive"))
      (node (ref "R17") (pin "1") (pinfunction "1_1") (pintype "passive"))
    )
    (net (code "70") (name "Net-(Q4-B)") (class "Default")
      (node (ref "Q4") (pin "1") (pinfunction "B_1") (pintype "passive"))
      (node (ref "R18") (pin "1") (pinfunction "1_1") (pintype "passive"))
    )
    (net (code "71") (name "Net-(Q6-B)") (class "Default")
      (node (ref "Q6") (pin "1") (pinfunction "B_1") (pintype "passive"))
      (node (ref "R24") (pin "1") (pinfunction "1_1") (pintype "passive"))
    )
    (net (code "72") (name "Net-(Q7-B)") (class "Default")
      (node (ref "Q7") (pin "1") (pinfunction "B_1") (pintype "passive"))
      (node (ref "R25") (pin "1") (pinfunction "1_1") (pintype "passive"))
    )
    (net (code "73") (name "OILP") (class "Default")
      (node (ref "J1") (pin "J2") (pinfunction "J_J2") (pintype "bidirectional"))
      (node (ref "U$1") (pin "P$12") (pinfunction "PE9_P$12") (pintype "bidirectional"))
    )
    (net (code "74") (name "REF") (class "Default")
      (node (ref "C18") (pin "+") (pinfunction "+_+") (pintype "passive"))
      (node (ref "U3") (pin "10") (pinfunction "REFOUT_10") (pintype "output"))
      (node (ref "U3") (pin "9") (pinfunction "REFIN_9") (pintype "input"))
    )
    (net (code "75") (name "RPM1") (class "Default")
      (node (ref "IC1") (pin "2") (pinfunction "O_2") (pintype "output"))
      (node (ref "U$1") (pin "P$45") (pinfunction "PC10_P$45") (pintype "bidirectional"))
    )
    (net (code "76") (name "RPM2") (class "Default")
      (node (ref "IC1") (pin "8") (pinfunction "O_8") (pintype "output"))
      (node (ref "U$1") (pin "P$46") (pinfunction "PC11_P$46") (pintype "bidirectional"))
    )
    (net (code "77") (name "RPM3") (class "Default")
      (node (ref "IC1") (pin "10") (pinfunction "O_10") (pintype "output"))
      (node (ref "U$1") (pin "P$47") (pinfunction "PC12_P$47") (pintype "bidirectional"))
    )
    (net (code "78") (name "RPM4") (class "Default")
      (node (ref "IC1") (pin "12") (pinfunction "O_12") (pintype "output"))
      (node (ref "U$1") (pin "P$48") (pinfunction "PD2_P$48") (pintype "bidirectional"))
    )
    (net (code "79") (name "RS232RX") (class "Default")
      (node (ref "J1") (pin "M1") (pinfunction "M_M1") (pintype "bidirectional"))
      (node (ref "U2") (pin "8") (pinfunction "R2IN_8") (pintype "input"))
    )
    (net (code "80") (name "RS232TX") (class "Default")
      (node (ref "J1") (pin "L1") (pinfunction "L_L1") (pintype "bidirectional"))
      (node (ref "U2") (pin "7") (pinfunction "T2OUT_7") (pintype "output"))
    )
    (net (code "81") (name "SCK") (class "Default")
      (node (ref "U$1") (pin "P$24") (pinfunction "PB13_P$24") (pintype "bidirectional"))
      (node (ref "U3") (pin "4") (pinfunction "SCLK_4") (pintype "input"))
    )
    (net (code "82") (name "SPEED") (class "Default")
      (node (ref "J1") (pin "G2") (pinfunction "G_G2") (pintype "bidirectional"))
      (node (ref "U$1") (pin "P$77") (pinfunction "PA2_P$77") (pintype "bidirectional"))
    )
    (net (code "83") (name "TRAVEL1") (class "Default")
      (node (ref "J1") (pin "C2") (pinfunction "C_C2") (pintype "bidirectional"))
      (node (ref "U$1") (pin "P$1") (pinfunction "PA3_P$1") (pintype "bidirectional"))
    )
    (net (code "84") (name "TRAVEL2") (class "Default")
      (node (ref "J1") (pin "C1") (pinfunction "C_C1") (pintype "bidirectional"))
      (node (ref "U$1") (pin "P$2") (pinfunction "PA4_P$2") (pintype "bidirectional"))
    )
    (net (code "85") (name "TRAVEL3") (class "Default")
      (node (ref "J1") (pin "C3") (pinfunction "C_C3") (pintype "bidirectional"))
      (node (ref "U$1") (pin "P$3") (pinfunction "PA5_P$3") (pintype "bidirectional"))
    )
    (net (code "86") (name "TRAVEL4") (class "Default")
      (node (ref "J1") (pin "C4") (pinfunction "C_C4") (pintype "bidirectional"))
      (node (ref "U$1") (pin "P$4") (pinfunction "PA6_P$4") (pintype "bidirectional"))
    )
    (net (code "87") (name "VOUT") (class "Default")
      (node (ref "J1") (pin "M2") (pinfunction "M_M2") (pintype "bidirectional"))
      (node (ref "U3") (pin "1") (pinfunction "BIPOFF_1") (pintype "passive"))
      (node (ref "U3") (pin "12") (pinfunction "VOUT_12") (pintype "output"))
      (node (ref "U3") (pin "14") (pinfunction "RFB_14") (pintype "passive"))
    )
    (net (code "88") (name "VTEMP") (class "Default")
      (node (ref "J1") (pin "H1") (pinfunction "H_H1") (pintype "bidirectional"))
      (node (ref "U$1") (pin "P$75") (pinfunction "PA0_P$75") (pintype "bidirectional"))
    )
    (net (code "89") (name "VTEMP2") (class "Default")
      (node (ref "J1") (pin "H3") (pinfunction "H_H3") (pintype "bidirectional"))
      (node (ref "U$1") (pin "P$74") (pinfunction "PC3_P$74") (pintype "bidirectional"))
    )
    (net (code "90") (name "YAW") (class "Default")
      (node (ref "J1") (pin "E2") (pinfunction "E_E2") (pintype "bidirectional"))
      (node (ref "R11") (pin "2") (pinfunction "2_2") (pintype "passive"))
    )
    (net (code "91") (name "YAWO") (class "Default")
      (node (ref "R11") (pin "1") (pinfunction "1_1") (pintype "passive"))
      (node (ref "R14") (pin "2") (pinfunction "2_2") (pintype "passive"))
      (node (ref "U$1") (pin "P$6") (pinfunction "PC4_P$6") (pintype "bidirectional"))
    )
    (net (code "92") (name "unconnected-(IC1E-O-Pad4)") (class "Default")
      (node (ref "IC1") (pin "4") (pinfunction "O_4") (pintype "output"))
    )
    (net (code "93") (name "unconnected-(IC1F-O-Pad6)") (class "Default")
      (node (ref "IC1") (pin "6") (pinfunction "O_6") (pintype "output"))
    )
    (net (code "94") (name "unconnected-(IC6E-O-Pad4)") (class "Default")
      (node (ref "IC6") (pin "4") (pinfunction "O_4") (pintype "output"))
    )
    (net (code "95") (name "unconnected-(IC6F-O-Pad6)") (class "Default")
      (node (ref "IC6") (pin "6") (pinfunction "O_6") (pintype "output"))
    )
    (net (code "96") (name "unconnected-(OK3-BAS-Pad6)") (class "Default")
      (node (ref "OK3") (pin "6") (pinfunction "BAS_6") (pintype "passive"))
    )
    (net (code "97") (name "unconnected-(OK4-BAS-Pad6)") (class "Default")
      (node (ref "OK4") (pin "6") (pinfunction "BAS_6") (pintype "passive"))
    )
    (net (code "98") (name "unconnected-(U$1A-PB10-PadP$21)") (class "Default")
      (node (ref "U$1") (pin "P$21") (pinfunction "PB10_P$21") (pintype "bidirectional"))
    )
    (net (code "99") (name "unconnected-(U$1A-PB11-PadP$22)") (class "Default")
      (node (ref "U$1") (pin "P$22") (pinfunction "PB11_P$22") (pintype "bidirectional"))
    )
    (net (code "100") (name "unconnected-(U$1A-PE10-PadP$13)") (class "Default")
      (node (ref "U$1") (pin "P$13") (pinfunction "PE10_P$13") (pintype "bidirectional"))
    )
    (net (code "101") (name "unconnected-(U$1A-PE11-PadP$14)") (class "Default")
      (node (ref "U$1") (pin "P$14") (pinfunction "PE11_P$14") (pintype "bidirectional"))
    )
    (net (code "102") (name "unconnected-(U$1A-PE12-PadP$15)") (class "Default")
      (node (ref "U$1") (pin "P$15") (pinfunction "PE12_P$15") (pintype "bidirectional"))
    )
    (net (code "103") (name "unconnected-(U$1A-PE13-PadP$16)") (class "Default")
      (node (ref "U$1") (pin "P$16") (pinfunction "PE13_P$16") (pintype "bidirectional"))
    )
    (net (code "104") (name "unconnected-(U$1A-PE14-PadP$17)") (class "Default")
      (node (ref "U$1") (pin "P$17") (pinfunction "PE14_P$17") (pintype "bidirectional"))
    )
    (net (code "105") (name "unconnected-(U$1A-PE15-PadP$18)") (class "Default")
      (node (ref "U$1") (pin "P$18") (pinfunction "PE15_P$18") (pintype "bidirectional"))
    )
    (net (code "106") (name "unconnected-(U$1B-PB12-PadP$23)") (class "Default")
      (node (ref "U$1") (pin "P$23") (pinfunction "PB12_P$23") (pintype "bidirectional"))
    )
    (net (code "107") (name "unconnected-(U$1B-PC6-PadP$35)") (class "Default")
      (node (ref "U$1") (pin "P$35") (pinfunction "PC6_P$35") (pintype "bidirectional"))
    )
    (net (code "108") (name "unconnected-(U$1B-PC7-PadP$36)") (class "Default")
      (node (ref "U$1") (pin "P$36") (pinfunction "PC7_P$36") (pintype "bidirectional"))
    )
    (net (code "109") (name "unconnected-(U$1B-PC8-PadP$37)") (class "Default")
      (node (ref "U$1") (pin "P$37") (pinfunction "PC8_P$37") (pintype "bidirectional"))
    )
    (net (code "110") (name "unconnected-(U$1B-PC9-PadP$38)") (class "Default")
      (node (ref "U$1") (pin "P$38") (pinfunction "PC9_P$38") (pintype "bidirectional"))
    )
    (net (code "111") (name "unconnected-(U$1B-PD9-PadP$28)") (class "Default")
      (node (ref "U$1") (pin "P$28") (pinfunction "PD9_P$28") (pintype "bidirectional"))
    )
    (net (code "112") (name "unconnected-(U$1B-PD11-PadP$30)") (class "Default")
      (node (ref "U$1") (pin "P$30") (pinfunction "PD11_P$30") (pintype "bidirectional"))
    )
    (net (code "113") (name "unconnected-(U$1B-PD13-PadP$32)") (class "Default")
      (node (ref "U$1") (pin "P$32") (pinfunction "PD13_P$32") (pintype "bidirectional"))
    )
    (net (code "114") (name "unconnected-(U$1B-PD15-PadP$34)") (class "Default")
      (node (ref "U$1") (pin "P$34") (pinfunction "PD15_P$34") (pintype "bidirectional"))
    )
    (net (code "115") (name "unconnected-(U$1C-PB4-PadP$54)") (class "Default")
      (node (ref "U$1") (pin "P$54") (pinfunction "PB4_P$54") (pintype "bidirectional"))
    )
    (net (code "116") (name "unconnected-(U$1C-PB7-PadP$57)") (class "Default")
      (node (ref "U$1") (pin "P$57") (pinfunction "PB7_P$57") (pintype "bidirectional"))
    )
    (net (code "117") (name "unconnected-(U$1C-PB8-PadP$58)") (class "Default")
      (node (ref "U$1") (pin "P$58") (pinfunction "PB8_P$58") (pintype "bidirectional"))
    )
    (net (code "118") (name "unconnected-(U$1C-PB9-PadP$59)") (class "Default")
      (node (ref "U$1") (pin "P$59") (pinfunction "PB9_P$59") (pintype "bidirectional"))
    )
    (net (code "119") (name "unconnected-(U$1C-PD3-PadP$49)") (class "Default")
      (node (ref "U$1") (pin "P$49") (pinfunction "PD3_P$49") (pintype "bidirectional"))
    )
    (net (code "120") (name "unconnected-(U$1C-PD4-PadP$50)") (class "Default")
      (node (ref "U$1") (pin "P$50") (pinfunction "PD4_P$50") (pintype "bidirectional"))
    )
    (net (code "121") (name "unconnected-(U$1C-PD5-PadP$51)") (class "Default")
      (node (ref "U$1") (pin "P$51") (pinfunction "PD5_P$51") (pintype "bidirectional"))
    )
    (net (code "122") (name "unconnected-(U$1C-PD6-PadP$52)") (class "Default")
      (node (ref "U$1") (pin "P$52") (pinfunction "PD6_P$52") (pintype "bidirectional"))
    )
    (net (code "123") (name "unconnected-(U$1C-PD7-PadP$53)") (class "Default")
      (node (ref "U$1") (pin "P$53") (pinfunction "PD7_P$53") (pintype "bidirectional"))
    )
    (net (code "124") (name "unconnected-(U$1C-PE0-PadP$60)") (class "Default")
      (node (ref "U$1") (pin "P$60") (pinfunction "PE0_P$60") (pintype "bidirectional"))
    )
    (net (code "125") (name "unconnected-(U$1C-PE1-PadP$61)") (class "Default")
      (node (ref "U$1") (pin "P$61") (pinfunction "PE1_P$61") (pintype "bidirectional"))
    )
    (net (code "126") (name "unconnected-(U$1D-PC0-PadP$71)") (class "Default")
      (node (ref "U$1") (pin "P$71") (pinfunction "PC0_P$71") (pintype "bidirectional"))
    )
    (net (code "127") (name "unconnected-(U$1D-PE2-PadP$63)") (class "Default")
      (node (ref "U$1") (pin "P$63") (pinfunction "PE2_P$63") (pintype "bidirectional"))
    )
    (net (code "128") (name "unconnected-(U$1D-PE3-PadP$64)") (class "Default")
      (node (ref "U$1") (pin "P$64") (pinfunction "PE3_P$64") (pintype "bidirectional"))
    )
    (net (code "129") (name "unconnected-(U$1D-PE4-PadP$65)") (class "Default")
      (node (ref "U$1") (pin "P$65") (pinfunction "PE4_P$65") (pintype "bidirectional"))
    )
    (net (code "130") (name "unconnected-(U$1D-PE5-PadP$66)") (class "Default")
      (node (ref "U$1") (pin "P$66") (pinfunction "PE5_P$66") (pintype "bidirectional"))
    )
    (net (code "131") (name "unconnected-(U2-R1IN-Pad13)") (class "Default")
      (node (ref "U2") (pin "13") (pinfunction "R1IN_13") (pintype "input"))
    )
    (net (code "132") (name "unconnected-(U2-R1OUT-Pad12)") (class "Default")
      (node (ref "U2") (pin "12") (pinfunction "R1OUT_12") (pintype "output"))
    )
    (net (code "133") (name "unconnected-(U2-T1IN-Pad11)") (class "Default")
      (node (ref "U2") (pin "11") (pinfunction "T1IN_11") (pintype "input"))
    )
    (net (code "134") (name "unconnected-(U2-T1OUT-Pad14)") (class "Default")
      (node (ref "U2") (pin "14") (pinfunction "T1OUT_14") (pintype "output"))
    )
  )
)
